# Claw_Machine_Final.net
KiCad netlist of a schematic drawn in EAGLE
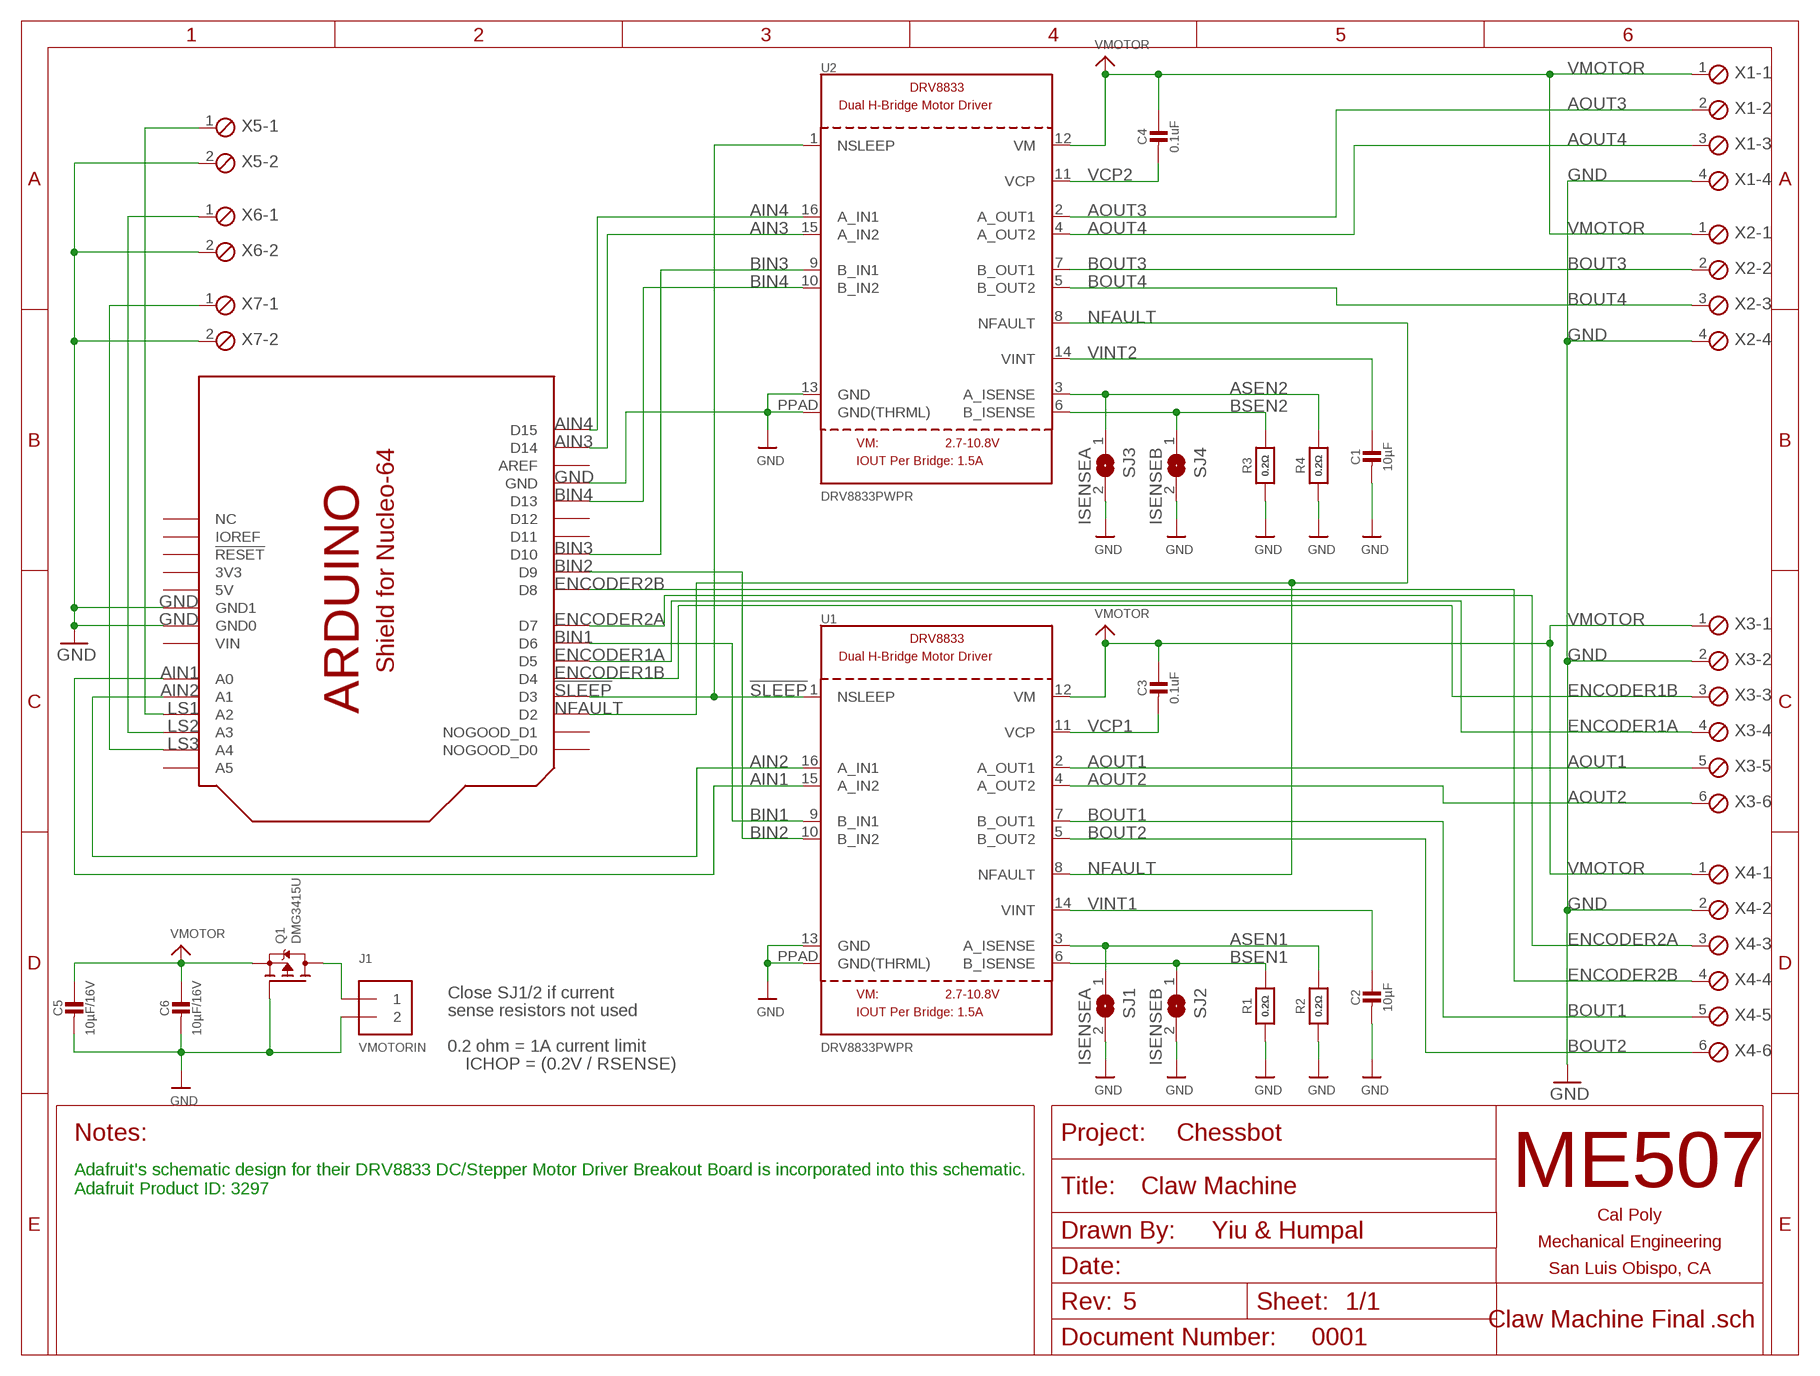
[diagram p0: schematic, sheet 1]

(export (version "E")
  (design (tool "Eeschema 10.0.6"))
  (components
    (comp (ref "C1")
      (value "10µF")
      (footprint "eagle-import:0805-NO")
      (libsource (lib "eagle-import") (part "CAP_CERAMIC0805-NOOUTLINE"))
    )
    (comp (ref "C2")
      (value "10µF")
      (footprint "eagle-import:0805-NO")
      (libsource (lib "eagle-import") (part "CAP_CERAMIC0805-NOOUTLINE"))
    )
    (comp (ref "C3")
      (value "0.1uF")
      (footprint "eagle-import:0805-NO")
      (libsource (lib "eagle-import") (part "CAP_CERAMIC0805-NOOUTLINE"))
    )
    (comp (ref "C4")
      (value "0.1uF")
      (footprint "eagle-import:0805-NO")
      (libsource (lib "eagle-import") (part "CAP_CERAMIC0805-NOOUTLINE"))
    )
    (comp (ref "C5")
      (value "10µF/16V")
      (footprint "eagle-import:0805-NO")
      (libsource (lib "eagle-import") (part "CAP_CERAMIC0805-NOOUTLINE"))
    )
    (comp (ref "C6")
      (value "10µF/16V")
      (footprint "eagle-import:0805-NO")
      (libsource (lib "eagle-import") (part "CAP_CERAMIC0805-NOOUTLINE"))
    )
    (comp (ref "J1")
      (value "VMOTORIN")
      (footprint "eagle-import:TERMBLOCK_1X2-3.5MM")
      (libsource (lib "eagle-import") (part "TERMBLOCK_1X2"))
    )
    (comp (ref "Q1")
      (value "DMG3415U")
      (footprint "eagle-import:SOT23-WIDE")
      (libsource (lib "eagle-import") (part "MOSFET-PWIDE"))
    )
    (comp (ref "R1")
      (value "0.2Ω")
      (footprint "eagle-import:_1206")
      (libsource (lib "eagle-import") (part "RESISTOR_1206"))
    )
    (comp (ref "R2")
      (value "0.2Ω")
      (footprint "eagle-import:_1206")
      (libsource (lib "eagle-import") (part "RESISTOR_1206"))
    )
    (comp (ref "R3")
      (value "0.2Ω")
      (footprint "eagle-import:_1206")
      (libsource (lib "eagle-import") (part "RESISTOR_1206"))
    )
    (comp (ref "R4")
      (value "0.2Ω")
      (footprint "eagle-import:_1206")
      (libsource (lib "eagle-import") (part "RESISTOR_1206"))
    )
    (comp (ref "SJ1")
      (value "ISENSEA")
      (footprint "eagle-import:SOLDERJUMPER_ARROW_NOPASTE")
      (libsource (lib "eagle-import") (part "SOLDERJUMPER"))
    )
    (comp (ref "SJ2")
      (value "ISENSEB")
      (footprint "eagle-import:SOLDERJUMPER_ARROW_NOPASTE")
      (libsource (lib "eagle-import") (part "SOLDERJUMPER"))
    )
    (comp (ref "SJ3")
      (value "ISENSEA")
      (footprint "eagle-import:SOLDERJUMPER_ARROW_NOPASTE")
      (libsource (lib "eagle-import") (part "SOLDERJUMPER"))
    )
    (comp (ref "SJ4")
      (value "ISENSEB")
      (footprint "eagle-import:SOLDERJUMPER_ARROW_NOPASTE")
      (libsource (lib "eagle-import") (part "SOLDERJUMPER"))
    )
    (comp (ref "U$1")
      (value "SHIELD_FOR_NUCLE0_64_STANDARD")
      (footprint "eagle-import:SHIELD_FOR_NUCLEO_64_STD")
      (libsource (lib "eagle-import") (part "SHIELD_FOR_NUCLE0_64_STANDARD"))
    )
    (comp (ref "U1")
      (value "DRV8833PWPR")
      (footprint "eagle-import:HTSSOP16")
      (libsource (lib "eagle-import") (part "DRV8833"))
    )
    (comp (ref "U2")
      (value "DRV8833PWPR")
      (footprint "eagle-import:HTSSOP16")
      (libsource (lib "eagle-import") (part "DRV8833"))
    )
    (comp (ref "X1")
      (value "SCREWTERM_4P_254")
      (footprint "eagle-import:4POL254")
      (libsource (lib "eagle-import") (part "SCREWTERM_4P_254"))
    )
    (comp (ref "X2")
      (value "SCREWTERM_4P_254")
      (footprint "eagle-import:4POL254")
      (libsource (lib "eagle-import") (part "SCREWTERM_4P_254"))
    )
    (comp (ref "X3")
      (value "SCREWTERM_6P_254")
      (footprint "eagle-import:6POL254")
      (libsource (lib "eagle-import") (part "SCREWTERM_6P_254"))
    )
    (comp (ref "X4")
      (value "SCREWTERM_6P_254")
      (footprint "eagle-import:6POL254")
      (libsource (lib "eagle-import") (part "SCREWTERM_6P_254"))
    )
    (comp (ref "X5")
      (value "SCREWTERM_2P_254")
      (footprint "eagle-import:2POL254")
      (libsource (lib "eagle-import") (part "SCREWTERM_2P_254"))
    )
    (comp (ref "X6")
      (value "SCREWTERM_2P_254")
      (footprint "eagle-import:2POL254")
      (libsource (lib "eagle-import") (part "SCREWTERM_2P_254"))
    )
    (comp (ref "X7")
      (value "SCREWTERM_2P_254")
      (footprint "eagle-import:2POL254")
      (libsource (lib "eagle-import") (part "SCREWTERM_2P_254"))
    )
  )
  (nets
    (net (code "1") (name "/3V3") (class "Default")
      (node (ref "U$1") (pin "3V") (pinfunction "3V3_3V") (pintype "power_in"))
    )
    (net (code "2") (name "/5V") (class "Default")
      (node (ref "U$1") (pin "5V") (pinfunction "5V_5V") (pintype "power_in"))
    )
    (net (code "3") (name "/AIN1") (class "Default")
      (node (ref "U$1") (pin "A0") (pinfunction "A0_A0") (pintype "bidirectional"))
      (node (ref "U1") (pin "15") (pinfunction "A_IN2_15") (pintype "input"))
    )
    (net (code "4") (name "/AIN2") (class "Default")
      (node (ref "U$1") (pin "A1") (pinfunction "A1_A1") (pintype "bidirectional"))
      (node (ref "U1") (pin "16") (pinfunction "A_IN1_16") (pintype "input"))
    )
    (net (code "5") (name "/AIN3") (class "Default")
      (node (ref "U$1") (pin "D14") (pinfunction "D14_D14") (pintype "bidirectional"))
      (node (ref "U2") (pin "15") (pinfunction "A_IN2_15") (pintype "input"))
    )
    (net (code "6") (name "/AIN4") (class "Default")
      (node (ref "U$1") (pin "D15") (pinfunction "D15_D15") (pintype "bidirectional"))
      (node (ref "U2") (pin "16") (pinfunction "A_IN1_16") (pintype "input"))
    )
    (net (code "7") (name "/AOUT1") (class "Default")
      (node (ref "U1") (pin "2") (pinfunction "A_OUT1_2") (pintype "output"))
      (node (ref "X3") (pin "5") (pinfunction "1_5") (pintype "passive"))
    )
    (net (code "8") (name "/AOUT2") (class "Default")
      (node (ref "U1") (pin "4") (pinfunction "A_OUT2_4") (pintype "output"))
      (node (ref "X3") (pin "6") (pinfunction "1_6") (pintype "passive"))
    )
    (net (code "9") (name "/AOUT3") (class "Default")
      (node (ref "U2") (pin "2") (pinfunction "A_OUT1_2") (pintype "output"))
      (node (ref "X1") (pin "2") (pinfunction "1_2") (pintype "passive"))
    )
    (net (code "10") (name "/AOUT4") (class "Default")
      (node (ref "U2") (pin "4") (pinfunction "A_OUT2_4") (pintype "output"))
      (node (ref "X1") (pin "3") (pinfunction "1_3") (pintype "passive"))
    )
    (net (code "11") (name "/ASEN1") (class "Default")
      (node (ref "R2") (pin "2") (pinfunction "2_2") (pintype "passive"))
      (node (ref "SJ1") (pin "1") (pinfunction "1_1") (pintype "passive"))
      (node (ref "U1") (pin "3") (pinfunction "A_ISENSE_3") (pintype "bidirectional"))
    )
    (net (code "12") (name "/ASEN2") (class "Default")
      (node (ref "R4") (pin "2") (pinfunction "2_2") (pintype "passive"))
      (node (ref "SJ3") (pin "1") (pinfunction "1_1") (pintype "passive"))
      (node (ref "U2") (pin "3") (pinfunction "A_ISENSE_3") (pintype "bidirectional"))
    )
    (net (code "13") (name "/BIN1") (class "Default")
      (node (ref "U$1") (pin "D6") (pinfunction "D6_D6") (pintype "bidirectional"))
      (node (ref "U1") (pin "9") (pinfunction "B_IN1_9") (pintype "input"))
    )
    (net (code "14") (name "/BIN2") (class "Default")
      (node (ref "U$1") (pin "D9") (pinfunction "D9_D9") (pintype "bidirectional"))
      (node (ref "U1") (pin "10") (pinfunction "B_IN2_10") (pintype "input"))
    )
    (net (code "15") (name "/BIN3") (class "Default")
      (node (ref "U$1") (pin "D10") (pinfunction "D10_D10") (pintype "bidirectional"))
      (node (ref "U2") (pin "9") (pinfunction "B_IN1_9") (pintype "input"))
    )
    (net (code "16") (name "/BIN4") (class "Default")
      (node (ref "U$1") (pin "D13") (pinfunction "D13_D13") (pintype "bidirectional"))
      (node (ref "U2") (pin "10") (pinfunction "B_IN2_10") (pintype "input"))
    )
    (net (code "17") (name "/BOUT1") (class "Default")
      (node (ref "U1") (pin "7") (pinfunction "B_OUT1_7") (pintype "output"))
      (node (ref "X4") (pin "5") (pinfunction "1_5") (pintype "passive"))
    )
    (net (code "18") (name "/BOUT2") (class "Default")
      (node (ref "U1") (pin "5") (pinfunction "B_OUT2_5") (pintype "output"))
      (node (ref "X4") (pin "6") (pinfunction "1_6") (pintype "passive"))
    )
    (net (code "19") (name "/BOUT3") (class "Default")
      (node (ref "U2") (pin "7") (pinfunction "B_OUT1_7") (pintype "output"))
      (node (ref "X2") (pin "2") (pinfunction "1_2") (pintype "passive"))
    )
    (net (code "20") (name "/BOUT4") (class "Default")
      (node (ref "U2") (pin "5") (pinfunction "B_OUT2_5") (pintype "output"))
      (node (ref "X2") (pin "3") (pinfunction "1_3") (pintype "passive"))
    )
    (net (code "21") (name "/BSEN1") (class "Default")
      (node (ref "R1") (pin "2") (pinfunction "2_2") (pintype "passive"))
      (node (ref "SJ2") (pin "1") (pinfunction "1_1") (pintype "passive"))
      (node (ref "U1") (pin "6") (pinfunction "B_ISENSE_6") (pintype "bidirectional"))
    )
    (net (code "22") (name "/BSEN2") (class "Default")
      (node (ref "R3") (pin "2") (pinfunction "2_2") (pintype "passive"))
      (node (ref "SJ4") (pin "1") (pinfunction "1_1") (pintype "passive"))
      (node (ref "U2") (pin "6") (pinfunction "B_ISENSE_6") (pintype "bidirectional"))
    )
    (net (code "23") (name "/ENCODER1A") (class "Default")
      (node (ref "U$1") (pin "D5") (pinfunction "D5_D5") (pintype "bidirectional"))
      (node (ref "X3") (pin "4") (pinfunction "1_4") (pintype "passive"))
    )
    (net (code "24") (name "/ENCODER1B") (class "Default")
      (node (ref "U$1") (pin "D4") (pinfunction "D4_D4") (pintype "bidirectional"))
      (node (ref "X3") (pin "3") (pinfunction "1_3") (pintype "passive"))
    )
    (net (code "25") (name "/ENCODER2A") (class "Default")
      (node (ref "U$1") (pin "D7") (pinfunction "D7_D7") (pintype "bidirectional"))
      (node (ref "X4") (pin "3") (pinfunction "1_3") (pintype "passive"))
    )
    (net (code "26") (name "/ENCODER2B") (class "Default")
      (node (ref "U$1") (pin "D8") (pinfunction "D8_D8") (pintype "bidirectional"))
      (node (ref "X4") (pin "4") (pinfunction "1_4") (pintype "passive"))
    )
    (net (code "27") (name "/LS1") (class "Default")
      (node (ref "U$1") (pin "A2") (pinfunction "A2_A2") (pintype "bidirectional"))
      (node (ref "X5") (pin "1") (pinfunction "1_1") (pintype "passive"))
    )
    (net (code "28") (name "/LS2") (class "Default")
      (node (ref "U$1") (pin "A3") (pinfunction "A3_A3") (pintype "bidirectional"))
      (node (ref "X6") (pin "1") (pinfunction "1_1") (pintype "passive"))
    )
    (net (code "29") (name "/LS3") (class "Default")
      (node (ref "U$1") (pin "A4") (pinfunction "A4_A4") (pintype "bidirectional"))
      (node (ref "X7") (pin "1") (pinfunction "1_1") (pintype "passive"))
    )
    (net (code "30") (name "/NFAULT") (class "Default")
      (node (ref "U$1") (pin "D2") (pinfunction "D2_D2") (pintype "bidirectional"))
      (node (ref "U1") (pin "8") (pinfunction "NFAULT_8") (pintype "bidirectional"))
      (node (ref "U2") (pin "8") (pinfunction "NFAULT_8") (pintype "bidirectional"))
    )
    (net (code "31") (name "/VCP1") (class "Default")
      (node (ref "C3") (pin "2") (pinfunction "2_2") (pintype "passive"))
      (node (ref "U1") (pin "11") (pinfunction "VCP_11") (pintype "bidirectional"))
    )
    (net (code "32") (name "/VCP2") (class "Default")
      (node (ref "C4") (pin "2") (pinfunction "2_2") (pintype "passive"))
      (node (ref "U2") (pin "11") (pinfunction "VCP_11") (pintype "bidirectional"))
    )
    (net (code "33") (name "/VIN") (class "Default")
      (node (ref "U$1") (pin "VIN") (pinfunction "VIN_VIN") (pintype "power_in"))
    )
    (net (code "34") (name "/VINT1") (class "Default")
      (node (ref "C2") (pin "1") (pinfunction "1_1") (pintype "passive"))
      (node (ref "U1") (pin "14") (pinfunction "VINT_14") (pintype "power_in"))
    )
    (net (code "35") (name "/VINT2") (class "Default")
      (node (ref "C1") (pin "1") (pinfunction "1_1") (pintype "passive"))
      (node (ref "U2") (pin "14") (pinfunction "VINT_14") (pintype "power_in"))
    )
    (net (code "36") (name "/~{SLEEP}") (class "Default")
      (node (ref "U$1") (pin "D3") (pinfunction "D3_D3") (pintype "bidirectional"))
      (node (ref "U1") (pin "1") (pinfunction "NSLEEP_1") (pintype "input"))
      (node (ref "U2") (pin "1") (pinfunction "NSLEEP_1") (pintype "input"))
    )
    (net (code "37") (name "GND") (class "Default")
      (node (ref "C1") (pin "2") (pinfunction "2_2") (pintype "passive"))
      (node (ref "C2") (pin "2") (pinfunction "2_2") (pintype "passive"))
      (node (ref "C5") (pin "2") (pinfunction "2_2") (pintype "passive"))
      (node (ref "C6") (pin "2") (pinfunction "2_2") (pintype "passive"))
      (node (ref "J1") (pin "2") (pinfunction "2_2") (pintype "passive"))
      (node (ref "Q1") (pin "1") (pinfunction "G_1") (pintype "passive"))
      (node (ref "R1") (pin "1") (pinfunction "1_1") (pintype "passive"))
      (node (ref "R2") (pin "1") (pinfunction "1_1") (pintype "passive"))
      (node (ref "R3") (pin "1") (pinfunction "1_1") (pintype "passive"))
      (node (ref "R4") (pin "1") (pinfunction "1_1") (pintype "passive"))
      (node (ref "SJ1") (pin "2") (pinfunction "2_2") (pintype "passive"))
      (node (ref "SJ2") (pin "2") (pinfunction "2_2") (pintype "passive"))
      (node (ref "SJ3") (pin "2") (pinfunction "2_2") (pintype "passive"))
      (node (ref "SJ4") (pin "2") (pinfunction "2_2") (pintype "passive"))
      (node (ref "U$1") (pin "GND") (pinfunction "GND_GND") (pintype "power_in"))
      (node (ref "U$1") (pin "GND1") (pinfunction "GND0_GND1") (pintype "power_in"))
      (node (ref "U$1") (pin "GND2") (pinfunction "GND1_GND2") (pintype "power_in"))
      (node (ref "U1") (pin "13") (pinfunction "GND_13") (pintype "power_in"))
      (node (ref "U1") (pin "PPAD") (pinfunction "GND(THRML)_PPAD") (pintype "power_in"))
      (node (ref "U2") (pin "13") (pinfunction "GND_13") (pintype "power_in"))
      (node (ref "U2") (pin "PPAD") (pinfunction "GND(THRML)_PPAD") (pintype "power_in"))
      (node (ref "X1") (pin "4") (pinfunction "1_4") (pintype "passive"))
      (node (ref "X2") (pin "4") (pinfunction "1_4") (pintype "passive"))
      (node (ref "X3") (pin "2") (pinfunction "1_2") (pintype "passive"))
      (node (ref "X4") (pin "2") (pinfunction "1_2") (pintype "passive"))
      (node (ref "X5") (pin "2") (pinfunction "1_2") (pintype "passive"))
      (node (ref "X6") (pin "2") (pinfunction "1_2") (pintype "passive"))
      (node (ref "X7") (pin "2") (pinfunction "1_2") (pintype "passive"))
    )
    (net (code "38") (name "Net-(Q1-D)") (class "Default")
      (node (ref "J1") (pin "1") (pinfunction "1_1") (pintype "passive"))
      (node (ref "Q1") (pin "3") (pinfunction "D_3") (pintype "passive"))
    )
    (net (code "39") (name "VMOTOR") (class "Default")
      (node (ref "C3") (pin "1") (pinfunction "1_1") (pintype "passive"))
      (node (ref "C4") (pin "1") (pinfunction "1_1") (pintype "passive"))
      (node (ref "C5") (pin "1") (pinfunction "1_1") (pintype "passive"))
      (node (ref "C6") (pin "1") (pinfunction "1_1") (pintype "passive"))
      (node (ref "Q1") (pin "2") (pinfunction "S_2") (pintype "passive"))
      (node (ref "U1") (pin "12") (pinfunction "VM_12") (pintype "power_in"))
      (node (ref "U2") (pin "12") (pinfunction "VM_12") (pintype "power_in"))
      (node (ref "X1") (pin "1") (pinfunction "1_1") (pintype "passive"))
      (node (ref "X2") (pin "1") (pinfunction "1_1") (pintype "passive"))
      (node (ref "X3") (pin "1") (pinfunction "1_1") (pintype "passive"))
      (node (ref "X4") (pin "1") (pinfunction "1_1") (pintype "passive"))
    )
    (net (code "40") (name "unconnected-(U$1-NOGOOD_D0-PadD0)") (class "Default")
      (node (ref "U$1") (pin "D0") (pinfunction "NOGOOD_D0_D0") (pintype "no_connect"))
    )
    (net (code "41") (name "unconnected-(U$1-NOGOOD_D1-PadD1)") (class "Default")
      (node (ref "U$1") (pin "D1") (pinfunction "NOGOOD_D1_D1") (pintype "no_connect"))
    )
    (net (code "42") (name "unconnected-(U$1-PadA5)") (class "Default")
      (node (ref "U$1") (pin "A5") (pinfunction "A5_A5") (pintype "bidirectional"))
    )
    (net (code "43") (name "unconnected-(U$1-PadAREF)") (class "Default")
      (node (ref "U$1") (pin "AREF") (pinfunction "AREF_AREF") (pintype "bidirectional"))
    )
    (net (code "44") (name "unconnected-(U$1-PadD11)") (class "Default")
      (node (ref "U$1") (pin "D11") (pinfunction "D11_D11") (pintype "bidirectional"))
    )
    (net (code "45") (name "unconnected-(U$1-PadD12)") (class "Default")
      (node (ref "U$1") (pin "D12") (pinfunction "D12_D12") (pintype "bidirectional"))
    )
    (net (code "46") (name "unconnected-(U$1-PadIOREF)") (class "Default")
      (node (ref "U$1") (pin "IOREF") (pinfunction "IOREF_IOREF") (pintype "bidirectional"))
    )
    (net (code "47") (name "unconnected-(U$1-PadNC)") (class "Default")
      (node (ref "U$1") (pin "NC") (pinfunction "NC_NC") (pintype "no_connect"))
    )
    (net (code "48") (name "unconnected-(U$1-~{RESET}-PadNRST)") (class "Default")
      (node (ref "U$1") (pin "NRST") (pinfunction "~{RESET}_NRST") (pintype "input"))
    )
  )
)
